# Optogenetic-stimulator-v1.net
KiCad netlist of a schematic drawn in EAGLE
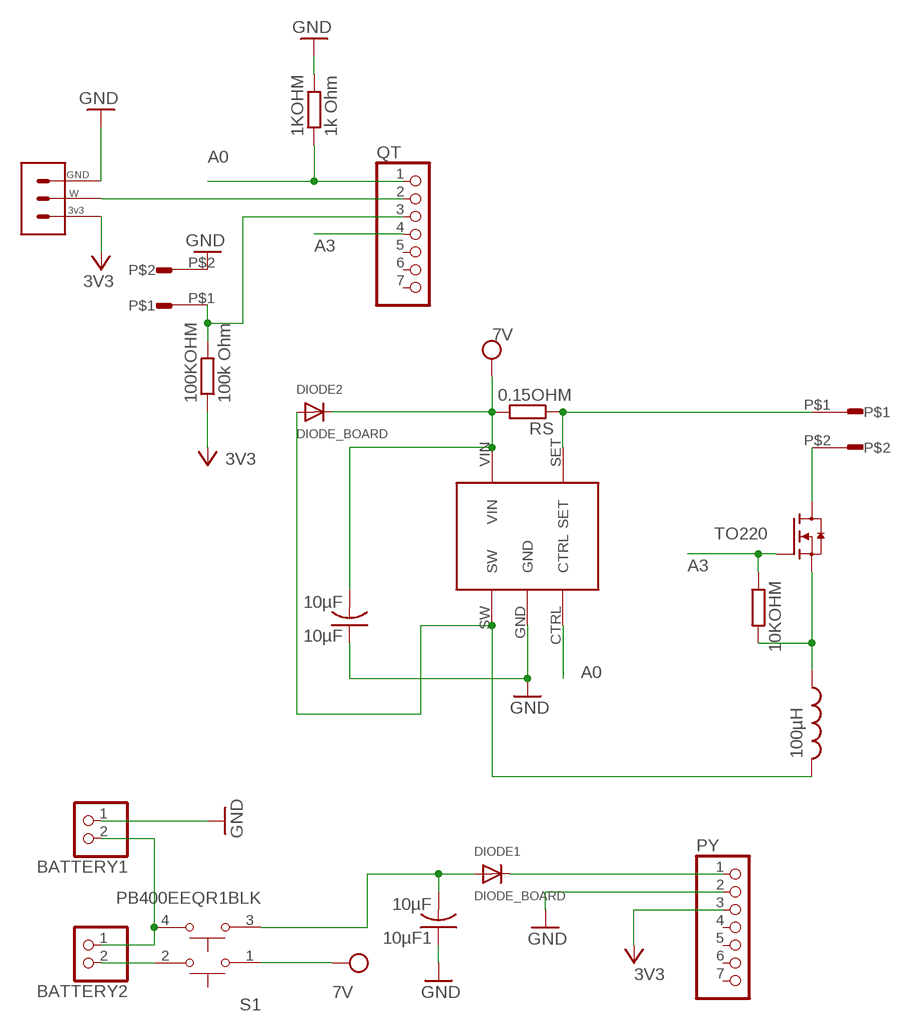
[diagram p0: schematic, sheet 1]

(export (version "E")
  (design (tool "Eeschema 10.0.6"))
  (components
    (comp (ref "1KOHM")
      (value "1k Ohm")
      (footprint "eagle-import:M1206")
      (libsource (lib "eagle-import") (part "R-EU_M1206"))
    )
    (comp (ref "10KOHM")
      (value "R-EU_M1206")
      (footprint "eagle-import:M1206")
      (libsource (lib "eagle-import") (part "R-EU_M1206"))
    )
    (comp (ref "10µF")
      (value "10µF")
      (footprint "eagle-import:C1206")
      (libsource (lib "eagle-import") (part "C-USC1206"))
    )
    (comp (ref "10µF1")
      (value "10µF")
      (footprint "eagle-import:C1206")
      (libsource (lib "eagle-import") (part "C-USC1206"))
    )
    (comp (ref "100KOHM")
      (value "100k Ohm")
      (footprint "eagle-import:M1206")
      (libsource (lib "eagle-import") (part "R-EU_M1206"))
    )
    (comp (ref "AL8860WT1")
      (value "AL8860WT")
      (footprint "eagle-import:AL8860WT")
      (libsource (lib "eagle-import") (part "AL8860WT"))
    )
    (comp (ref "BATTERY1")
      (value "JST_2PIN-THM")
      (footprint "eagle-import:JST-PH-2-THM")
      (libsource (lib "eagle-import") (part "JST_2PIN-THM"))
    )
    (comp (ref "BATTERY2")
      (value "JST_2PIN-THM")
      (footprint "eagle-import:JST-PH-2-THM")
      (libsource (lib "eagle-import") (part "JST_2PIN-THM"))
    )
    (comp (ref "DIODE1")
      (value "DIODE_BOARD")
      (footprint "eagle-import:DIODE")
      (libsource (lib "eagle-import") (part "DIODE_BOARD"))
    )
    (comp (ref "DIODE2")
      (value "DIODE_BOARD")
      (footprint "eagle-import:DIODE")
      (libsource (lib "eagle-import") (part "DIODE_BOARD"))
    )
    (comp (ref "LED")
      (value "UNIVERSAL_PAD")
      (footprint "eagle-import:UNIVERSAL_PAD")
      (libsource (lib "eagle-import") (part "UNIVERSAL_PAD"))
    )
    (comp (ref "NTC")
      (value "UNIVERSAL_PAD")
      (footprint "eagle-import:UNIVERSAL_PAD")
      (libsource (lib "eagle-import") (part "UNIVERSAL_PAD"))
    )
    (comp (ref "PY")
      (value "PINHD-1X7")
      (footprint "eagle-import:1X07")
      (libsource (lib "eagle-import") (part "PINHD-1X7"))
    )
    (comp (ref "QT")
      (value "PINHD-1X7")
      (footprint "eagle-import:1X07")
      (libsource (lib "eagle-import") (part "PINHD-1X7"))
    )
    (comp (ref "RS")
      (value "0.15OHM")
      (footprint "eagle-import:M1206")
      (libsource (lib "eagle-import") (part "R-EU_M1206"))
    )
    (comp (ref "S1")
      (value "PB400EEQR1BLK")
      (footprint "eagle-import:SW_PB400EEQR1BLK")
      (fields (field (name "MF") "E-Switch"))
      (libsource (lib "eagle-import") (part "PB400EEQR1BLK"))
    )
    (comp (ref "TO220")
      (value "MOSFET-TO220")
      (footprint "eagle-import:TO220")
      (libsource (lib "eagle-import") (part "MOSFET-TO220"))
    )
    (comp (ref "U$1")
      (value "BOARD_INDUCTOR")
      (footprint "eagle-import:INDUCTOR")
      (libsource (lib "eagle-import") (part "BOARD_INDUCTOR"))
    )
    (comp (ref "U$6")
      (value "POTENTIOMETER_BOARD")
      (footprint "eagle-import:POTENTIOMETER_BOARD")
      (libsource (lib "eagle-import") (part "POTENTIOMETER_BOARD"))
    )
  )
  (nets
    (net (code "1") (name "/A0") (class "Default")
      (node (ref "1KOHM") (pin "1") (pinfunction "1_1") (pintype "passive"))
      (node (ref "AL8860WT1") (pin "CTRL") (pinfunction "CTRL_CTRL") (pintype "bidirectional"))
      (node (ref "QT") (pin "1") (pinfunction "1_1") (pintype "passive"))
    )
    (net (code "2") (name "/A3") (class "Default")
      (node (ref "10KOHM") (pin "1") (pinfunction "1_1") (pintype "passive"))
      (node (ref "QT") (pin "4") (pinfunction "4_4") (pintype "passive"))
      (node (ref "TO220") (pin "1") (pinfunction "G_1") (pintype "passive"))
    )
    (net (code "3") (name "3v3") (class "Default")
      (node (ref "100KOHM") (pin "1") (pinfunction "1_1") (pintype "passive"))
      (node (ref "PY") (pin "3") (pinfunction "3_3") (pintype "passive"))
      (node (ref "U$6") (pin "3V3") (pinfunction "3V3_3V3") (pintype "passive"))
    )
    (net (code "4") (name "7 V") (class "Default")
      (node (ref "10µF") (pin "2") (pinfunction "2_2") (pintype "passive"))
      (node (ref "AL8860WT1") (pin "VIN") (pinfunction "VIN_VIN") (pintype "bidirectional"))
      (node (ref "DIODE2") (pin "P$2") (pinfunction "C_P$2") (pintype "passive"))
      (node (ref "RS") (pin "2") (pinfunction "2_2") (pintype "passive"))
      (node (ref "S1") (pin "1") (pinfunction "1_1") (pintype "passive"))
    )
    (net (code "5") (name "GND") (class "Default")
      (node (ref "10µF") (pin "1") (pinfunction "1_1") (pintype "passive"))
      (node (ref "10µF1") (pin "1") (pinfunction "1_1") (pintype "passive"))
      (node (ref "1KOHM") (pin "2") (pinfunction "2_2") (pintype "passive"))
      (node (ref "AL8860WT1") (pin "GND") (pinfunction "GND_GND") (pintype "bidirectional"))
      (node (ref "BATTERY1") (pin "1") (pinfunction "2_1") (pintype "passive"))
      (node (ref "NTC") (pin "P$2") (pinfunction "P$2_P$2") (pintype "bidirectional"))
      (node (ref "PY") (pin "2") (pinfunction "2_2") (pintype "passive"))
      (node (ref "U$6") (pin "GND") (pinfunction "GND_GND") (pintype "passive"))
    )
    (net (code "6") (name "Net-(100KOHM-Pad2)") (class "Default")
      (node (ref "100KOHM") (pin "2") (pinfunction "2_2") (pintype "passive"))
      (node (ref "NTC") (pin "P$1") (pinfunction "P$1_P$1") (pintype "bidirectional"))
      (node (ref "QT") (pin "3") (pinfunction "3_3") (pintype "passive"))
    )
    (net (code "7") (name "Net-(AL8860WT1-PadSET)") (class "Default")
      (node (ref "AL8860WT1") (pin "SET") (pinfunction "SET_SET") (pintype "bidirectional"))
      (node (ref "LED") (pin "P$1") (pinfunction "P$1_P$1") (pintype "bidirectional"))
      (node (ref "RS") (pin "1") (pinfunction "1_1") (pintype "passive"))
    )
    (net (code "8") (name "Net-(BATTERY1-1)") (class "Default")
      (node (ref "BATTERY1") (pin "2") (pinfunction "1_2") (pintype "passive"))
      (node (ref "BATTERY2") (pin "1") (pinfunction "2_1") (pintype "passive"))
      (node (ref "S1") (pin "4") (pinfunction "4_4") (pintype "passive"))
    )
    (net (code "9") (name "Net-(BATTERY2-1)") (class "Default")
      (node (ref "BATTERY2") (pin "2") (pinfunction "1_2") (pintype "passive"))
      (node (ref "S1") (pin "2") (pinfunction "2_2") (pintype "passive"))
    )
    (net (code "10") (name "Net-(DIODE1-A)") (class "Default")
      (node (ref "10µF1") (pin "2") (pinfunction "2_2") (pintype "passive"))
      (node (ref "DIODE1") (pin "P$1") (pinfunction "A_P$1") (pintype "passive"))
      (node (ref "S1") (pin "3") (pinfunction "3_3") (pintype "passive"))
    )
    (net (code "11") (name "Net-(DIODE1-C)") (class "Default")
      (node (ref "DIODE1") (pin "P$2") (pinfunction "C_P$2") (pintype "passive"))
      (node (ref "PY") (pin "1") (pinfunction "1_1") (pintype "passive"))
    )
    (net (code "12") (name "Net-(DIODE2-A)") (class "Default")
      (node (ref "AL8860WT1") (pin "SW") (pinfunction "SW_SW") (pintype "bidirectional"))
      (node (ref "DIODE2") (pin "P$1") (pinfunction "A_P$1") (pintype "passive"))
      (node (ref "U$1") (pin "P$2") (pinfunction "2_P$2") (pintype "passive"))
    )
    (net (code "13") (name "Net-(QT-Pad2)") (class "Default")
      (node (ref "QT") (pin "2") (pinfunction "2_2") (pintype "passive"))
      (node (ref "U$6") (pin "W") (pinfunction "W_W") (pintype "passive"))
    )
    (net (code "14") (name "Net-(TO220-D)") (class "Default")
      (node (ref "LED") (pin "P$2") (pinfunction "P$2_P$2") (pintype "bidirectional"))
      (node (ref "TO220") (pin "2") (pinfunction "D_2") (pintype "passive"))
    )
    (net (code "15") (name "Net-(TO220-S)") (class "Default")
      (node (ref "10KOHM") (pin "2") (pinfunction "2_2") (pintype "passive"))
      (node (ref "TO220") (pin "3") (pinfunction "S_3") (pintype "passive"))
      (node (ref "U$1") (pin "P$1") (pinfunction "1_P$1") (pintype "passive"))
    )
    (net (code "16") (name "unconnected-(PY-Pad4)") (class "Default")
      (node (ref "PY") (pin "4") (pinfunction "4_4") (pintype "passive"))
    )
    (net (code "17") (name "unconnected-(PY-Pad5)") (class "Default")
      (node (ref "PY") (pin "5") (pinfunction "5_5") (pintype "passive"))
    )
    (net (code "18") (name "unconnected-(PY-Pad6)") (class "Default")
      (node (ref "PY") (pin "6") (pinfunction "6_6") (pintype "passive"))
    )
    (net (code "19") (name "unconnected-(PY-Pad7)") (class "Default")
      (node (ref "PY") (pin "7") (pinfunction "7_7") (pintype "passive"))
    )
    (net (code "20") (name "unconnected-(QT-Pad5)") (class "Default")
      (node (ref "QT") (pin "5") (pinfunction "5_5") (pintype "passive"))
    )
    (net (code "21") (name "unconnected-(QT-Pad6)") (class "Default")
      (node (ref "QT") (pin "6") (pinfunction "6_6") (pintype "passive"))
    )
    (net (code "22") (name "unconnected-(QT-Pad7)") (class "Default")
      (node (ref "QT") (pin "7") (pinfunction "7_7") (pintype "passive"))
    )
  )
)
